# RD.net
KiCad netlist of a schematic drawn in Altium Designer
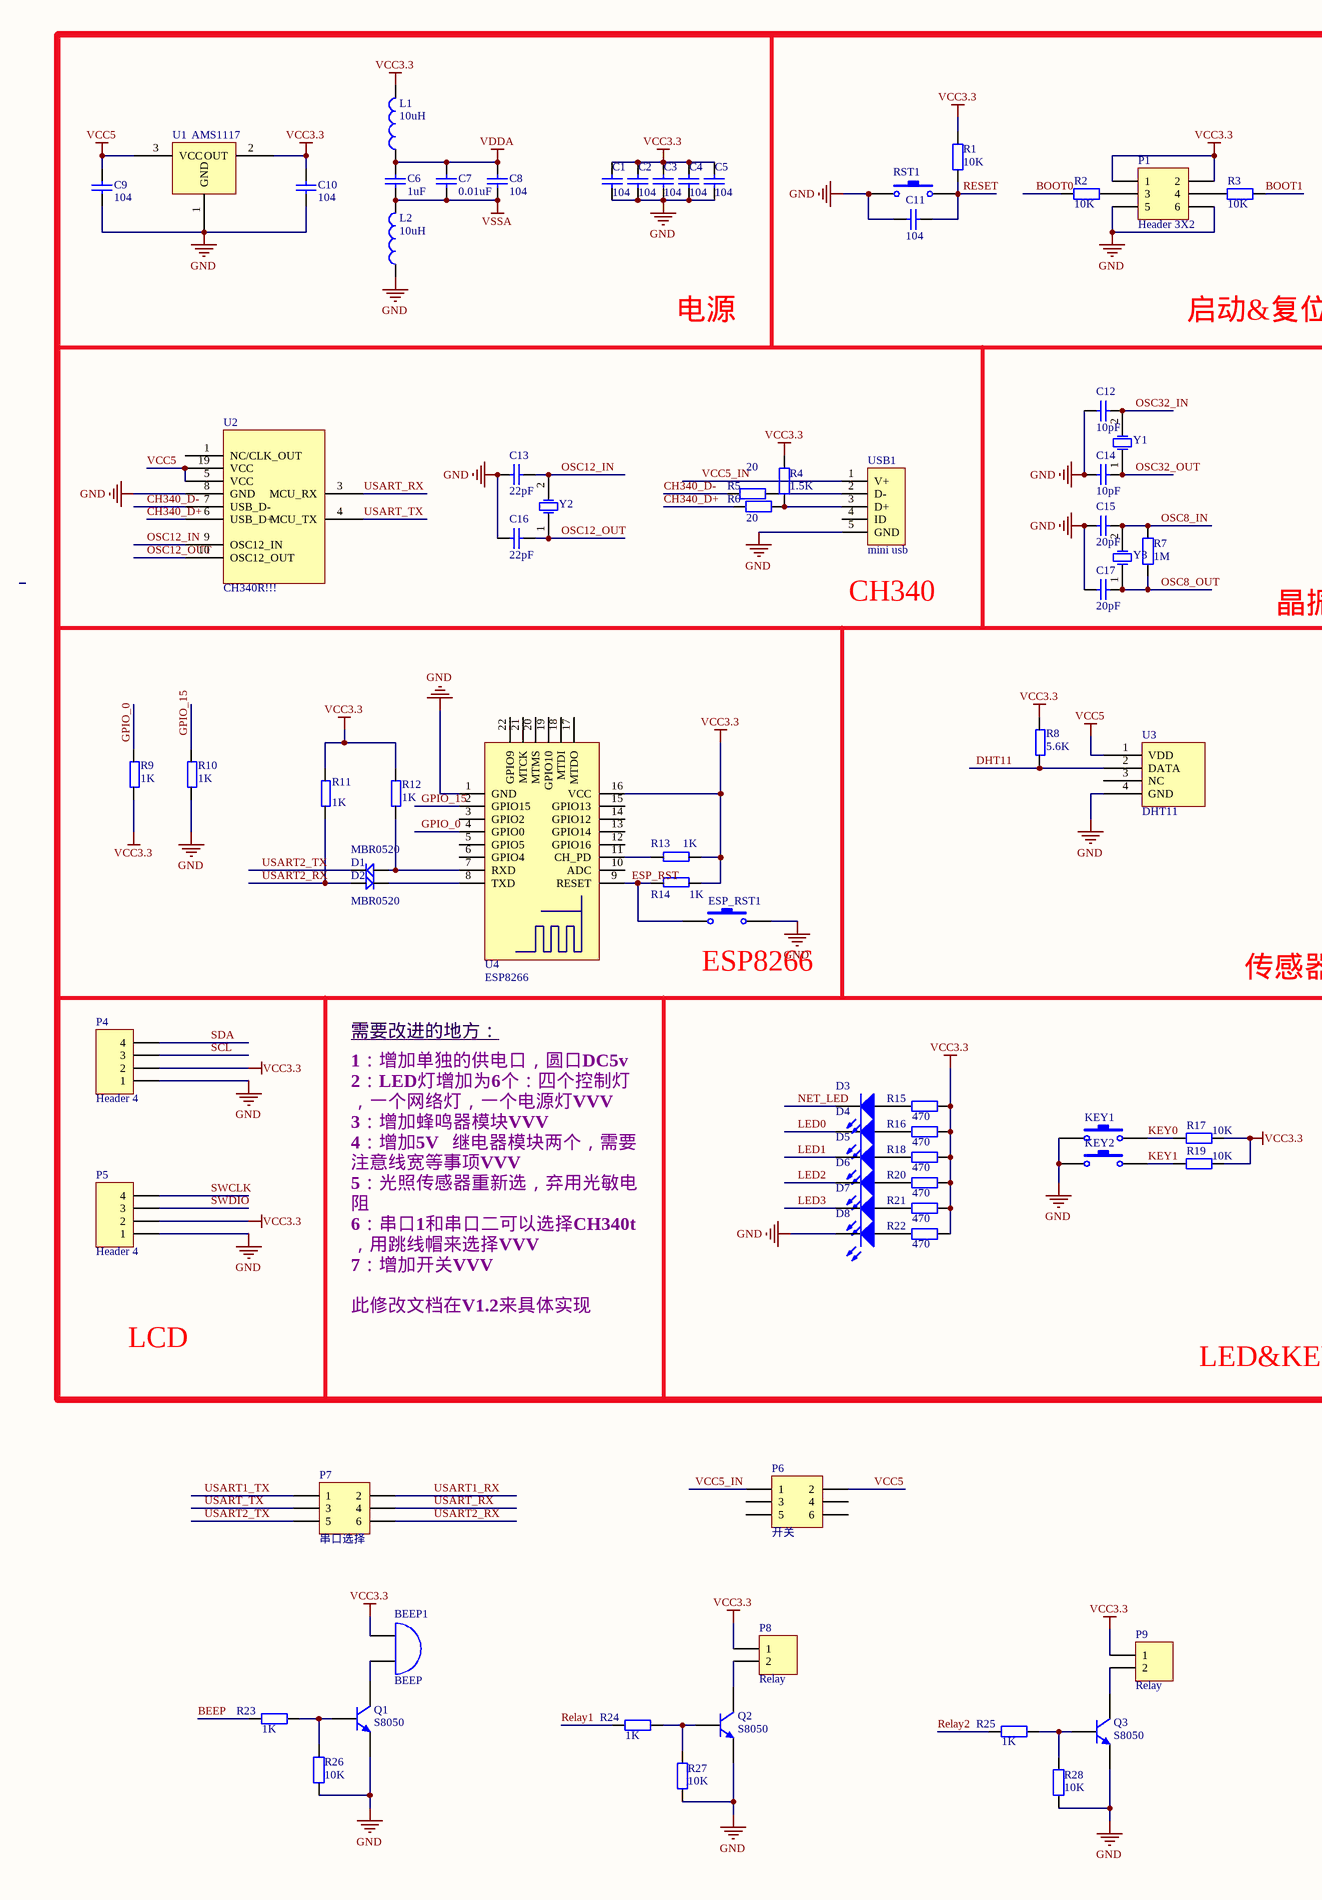
[diagram p0: 云RD.SchDoc, left]
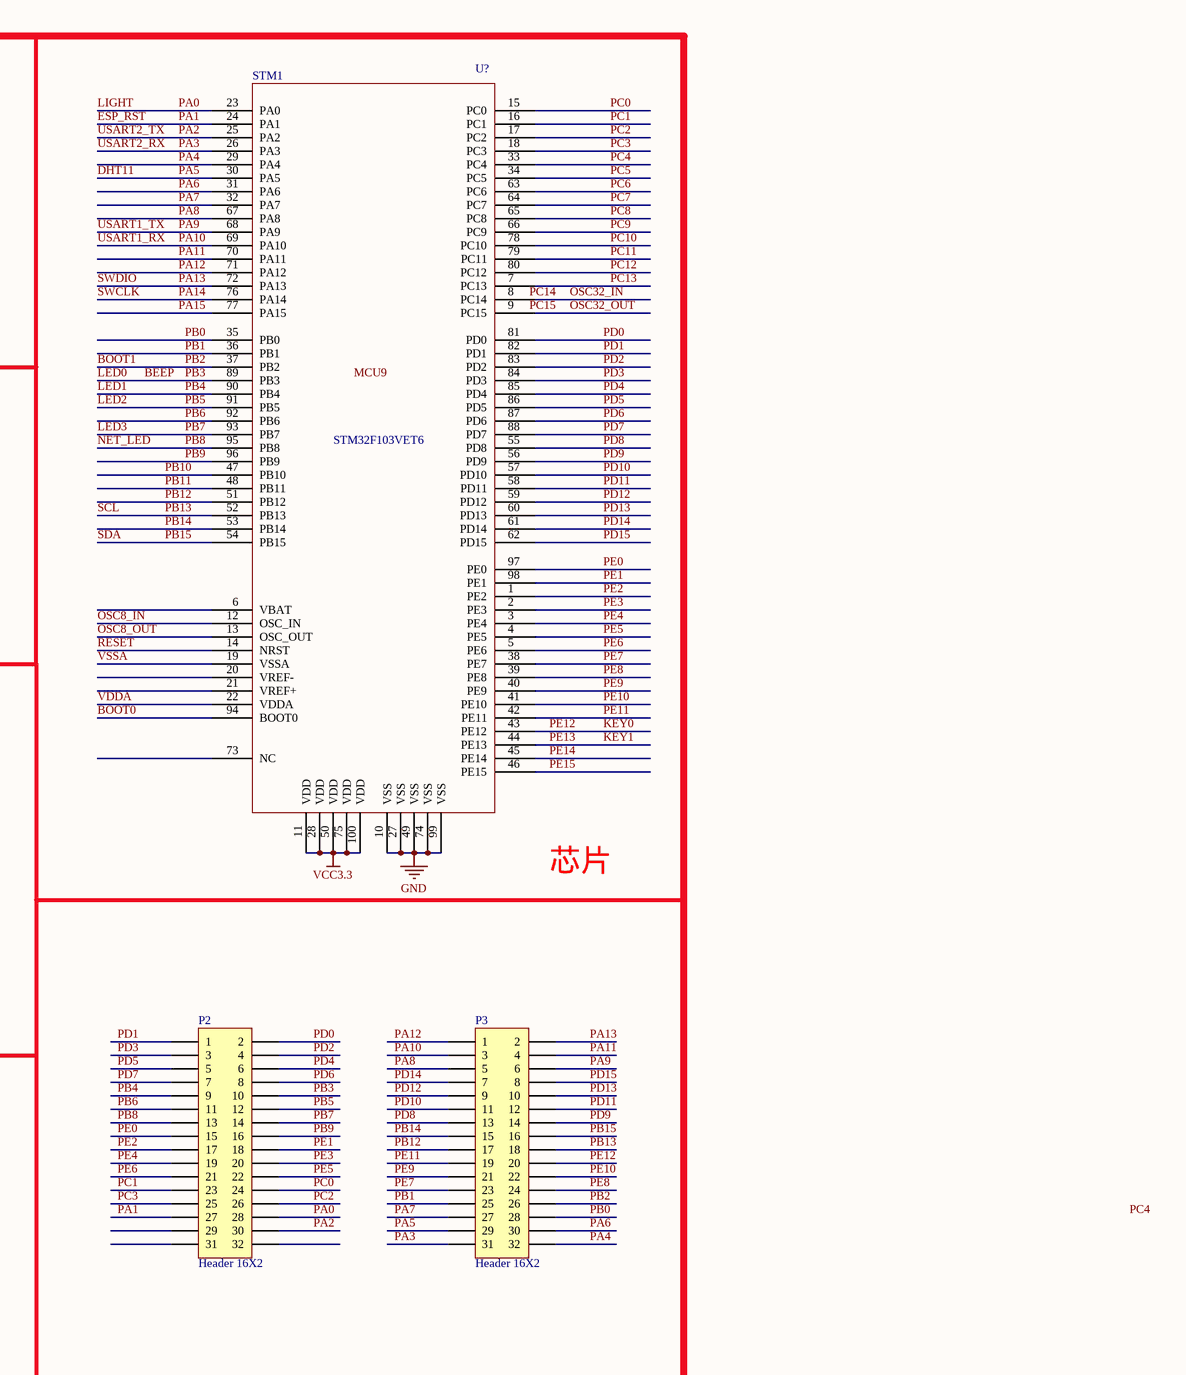
[diagram p1: 云RD.SchDoc, right]

(export (version "E")
  (design (tool "Eeschema 10.0.6"))
  (components
    (comp (ref "BEEP1")
      (value "BEEP")
      (footprint "BEEP")
      (description "Electrical Bell")
      (fields (field (name "PUBLISHER") "Altium Limited"))
      (libsource (lib "Miscellaneous Devices") (part "Bell"))
    )
    (comp (ref "C1")
      (value "104")
      (footprint "0805")
      (description "Capacitor")
      (fields (field (name "Comment") "Cap") (field (name "PUBLISHER") "Altium Limited"))
      (libsource (lib "Miscellaneous Devices") (part "Cap"))
    )
    (comp (ref "C2")
      (value "104")
      (footprint "0805")
      (description "Capacitor")
      (fields (field (name "Comment") "Cap") (field (name "PUBLISHER") "Altium Limited"))
      (libsource (lib "Miscellaneous Devices") (part "Cap"))
    )
    (comp (ref "C3")
      (value "104")
      (footprint "0805")
      (description "Capacitor")
      (fields (field (name "Comment") "Cap") (field (name "PUBLISHER") "Altium Limited"))
      (libsource (lib "Miscellaneous Devices") (part "Cap"))
    )
    (comp (ref "C4")
      (value "104")
      (footprint "0805")
      (description "Capacitor")
      (fields (field (name "Comment") "Cap") (field (name "PUBLISHER") "Altium Limited"))
      (libsource (lib "Miscellaneous Devices") (part "Cap"))
    )
    (comp (ref "C5")
      (value "104")
      (footprint "0805")
      (description "Capacitor")
      (fields (field (name "Comment") "Cap") (field (name "PUBLISHER") "Altium Limited"))
      (libsource (lib "Miscellaneous Devices") (part "Cap"))
    )
    (comp (ref "C6")
      (value "1uF")
      (footprint "0805")
      (description "Capacitor")
      (fields (field (name "Comment") "Cap") (field (name "PUBLISHER") "Altium Limited"))
      (libsource (lib "Miscellaneous Devices") (part "Cap"))
    )
    (comp (ref "C7")
      (value "0.01uF")
      (footprint "0805")
      (description "Capacitor")
      (fields (field (name "Comment") "Cap") (field (name "PUBLISHER") "Altium Limited"))
      (libsource (lib "Miscellaneous Devices") (part "Cap"))
    )
    (comp (ref "C8")
      (value "104")
      (footprint "0805")
      (description "Capacitor")
      (fields (field (name "Comment") "Cap") (field (name "PUBLISHER") "Altium Limited"))
      (libsource (lib "Miscellaneous Devices") (part "Cap"))
    )
    (comp (ref "C9")
      (value "104")
      (footprint "0805")
      (description "Capacitor")
      (fields (field (name "Comment") "Cap") (field (name "PUBLISHER") "Altium Limited"))
      (libsource (lib "Miscellaneous Devices") (part "Cap"))
    )
    (comp (ref "C10")
      (value "104")
      (footprint "0805")
      (description "Capacitor")
      (fields (field (name "Comment") "Cap") (field (name "PUBLISHER") "Altium Limited"))
      (libsource (lib "Miscellaneous Devices") (part "Cap"))
    )
    (comp (ref "C11")
      (value "104")
      (footprint "0805")
      (description "Capacitor")
      (fields (field (name "Comment") "Cap") (field (name "PUBLISHER") "Altium Limited"))
      (libsource (lib "Miscellaneous Devices") (part "Cap"))
    )
    (comp (ref "C12")
      (value "10pF")
      (footprint "0805")
      (description "Capacitor")
      (fields (field (name "Comment") "Cap") (field (name "PUBLISHER") "Altium Limited"))
      (libsource (lib "Miscellaneous Devices") (part "Cap"))
    )
    (comp (ref "C13")
      (value "22pF")
      (footprint "0805")
      (description "Capacitor")
      (fields (field (name "Comment") "Cap") (field (name "PUBLISHER") "Altium Limited"))
      (libsource (lib "Miscellaneous Devices") (part "Cap"))
    )
    (comp (ref "C14")
      (value "10pF")
      (footprint "0805")
      (description "Capacitor")
      (fields (field (name "Comment") "Cap") (field (name "PUBLISHER") "Altium Limited"))
      (libsource (lib "Miscellaneous Devices") (part "Cap"))
    )
    (comp (ref "C15")
      (value "20pF")
      (footprint "0805")
      (description "Capacitor")
      (fields (field (name "Comment") "Cap") (field (name "PUBLISHER") "Altium Limited"))
      (libsource (lib "Miscellaneous Devices") (part "Cap"))
    )
    (comp (ref "C16")
      (value "22pF")
      (footprint "0805")
      (description "Capacitor")
      (fields (field (name "Comment") "Cap") (field (name "PUBLISHER") "Altium Limited"))
      (libsource (lib "Miscellaneous Devices") (part "Cap"))
    )
    (comp (ref "C17")
      (value "20pF")
      (footprint "0805")
      (description "Capacitor")
      (fields (field (name "Comment") "Cap") (field (name "PUBLISHER") "Altium Limited"))
      (libsource (lib "Miscellaneous Devices") (part "Cap"))
    )
    (comp (ref "D1")
      (value "MBR0520")
      (footprint "SOD-123")
      (description "1N4148")
      (libsource (lib "ESP8266V1.2") (part "D"))
    )
    (comp (ref "D2")
      (value "MBR0520")
      (footprint "SOD-123")
      (description "1N4148")
      (libsource (lib "ESP8266V1.2") (part "D"))
    )
    (comp (ref "D3")
      (value "LED1")
      (footprint "0805")
      (description "Typical RED GaAs LED")
      (fields (field (name "PUBLISHER") "Altium Limited"))
      (libsource (lib "Miscellaneous Devices") (part "LED1"))
    )
    (comp (ref "D4")
      (value "LED1")
      (footprint "0805")
      (description "Typical RED GaAs LED")
      (fields (field (name "PUBLISHER") "Altium Limited"))
      (libsource (lib "Miscellaneous Devices") (part "LED1"))
    )
    (comp (ref "D5")
      (value "LED1")
      (footprint "0805")
      (description "Typical RED GaAs LED")
      (fields (field (name "PUBLISHER") "Altium Limited"))
      (libsource (lib "Miscellaneous Devices") (part "LED1"))
    )
    (comp (ref "D6")
      (value "LED1")
      (footprint "0805")
      (description "Typical RED GaAs LED")
      (fields (field (name "PUBLISHER") "Altium Limited"))
      (libsource (lib "Miscellaneous Devices") (part "LED1"))
    )
    (comp (ref "D7")
      (value "LED1")
      (footprint "0805")
      (description "Typical RED GaAs LED")
      (fields (field (name "PUBLISHER") "Altium Limited"))
      (libsource (lib "Miscellaneous Devices") (part "LED1"))
    )
    (comp (ref "D8")
      (value "LED1")
      (footprint "0805")
      (description "Typical RED GaAs LED")
      (fields (field (name "PUBLISHER") "Altium Limited"))
      (libsource (lib "Miscellaneous Devices") (part "LED1"))
    )
    (comp (ref "ESP_RST1")
      (value "SW-PB")
      (footprint "PUSHSW")
      (description "Switch")
      (fields (field (name "PUBLISHER") "Altium Limited"))
      (libsource (lib "gtm900") (part "SW-PB"))
    )
    (comp (ref "KEY1")
      (value "SW-PB")
      (footprint "PUSHSW")
      (description "Switch")
      (fields (field (name "PUBLISHER") "Altium Limited"))
      (libsource (lib "gtm900") (part "SW-PB"))
    )
    (comp (ref "KEY2")
      (value "SW-PB")
      (footprint "PUSHSW")
      (description "Switch")
      (fields (field (name "PUBLISHER") "Altium Limited"))
      (libsource (lib "gtm900") (part "SW-PB"))
    )
    (comp (ref "L1")
      (value "10uH")
      (footprint "0805")
      (description "Inductor")
      (fields (field (name "PUBLISHER") "Altium Limited"))
      (libsource (lib "Miscellaneous Devices") (part "Inductor"))
    )
    (comp (ref "L2")
      (value "10uH")
      (footprint "0805")
      (description "Inductor")
      (fields (field (name "PUBLISHER") "Altium Limited"))
      (libsource (lib "Miscellaneous Devices") (part "Inductor"))
    )
    (comp (ref "P1")
      (value "Header 3X2")
      (footprint "HDR2X3")
      (description "Header, 3-Pin, Dual row")
      (fields (field (name "PUBLISHER") "Altium Limited"))
      (libsource (lib "Miscellaneous Connectors") (part "Header 3X2"))
    )
    (comp (ref "P2")
      (value "Header 16X2")
      (footprint "HDR2X16")
      (description "Header, 16-Pin, Dual row")
      (fields (field (name "PUBLISHER") "Altium Limited"))
      (libsource (lib "Miscellaneous Connectors") (part "Header 16X2"))
    )
    (comp (ref "P3")
      (value "Header 16X2")
      (footprint "HDR2X16")
      (description "Header, 16-Pin, Dual row")
      (fields (field (name "PUBLISHER") "Altium Limited"))
      (libsource (lib "Miscellaneous Connectors") (part "Header 16X2"))
    )
    (comp (ref "P4")
      (value "Header 4")
      (footprint "0.96_OLED")
      (description "Header, 4-Pin")
      (fields (field (name "PUBLISHER") "Altium Limited"))
      (libsource (lib "Miscellaneous Connectors") (part "Header 4"))
    )
    (comp (ref "P5")
      (value "Header 4")
      (footprint "HDR1X4")
      (description "Header, 4-Pin")
      (fields (field (name "PUBLISHER") "Altium Limited"))
      (libsource (lib "Miscellaneous Connectors") (part "Header 4"))
    )
    (comp (ref "P6")
      (value "开关")
      (footprint "开关")
      (description "Header, 3-Pin, Dual row")
      (fields (field (name "PUBLISHER") "Altium Limited"))
      (libsource (lib "Miscellaneous Connectors") (part "Header 3X2"))
    )
    (comp (ref "P7")
      (value "串口选择")
      (footprint "HDR2X3")
      (description "Header, 3-Pin, Dual row")
      (fields (field (name "PUBLISHER") "Altium Limited"))
      (libsource (lib "Miscellaneous Connectors") (part "Header 3X2"))
    )
    (comp (ref "P8")
      (value "Relay")
      (footprint "BEEP")
      (description "Header, 2-Pin")
      (fields (field (name "PUBLISHER") "Altium Limited"))
      (libsource (lib "Miscellaneous Connectors") (part "Header 2"))
    )
    (comp (ref "P9")
      (value "Relay")
      (footprint "BEEP")
      (description "Header, 2-Pin")
      (fields (field (name "PUBLISHER") "Altium Limited"))
      (libsource (lib "Miscellaneous Connectors") (part "Header 2"))
    )
    (comp (ref "Q1")
      (value "S8050")
      (footprint "SOT-23")
      (description "NPN Bipolar Transistor")
      (fields (field (name "PUBLISHER") "Altium Limited"))
      (libsource (lib "Miscellaneous Devices") (part "NPN"))
    )
    (comp (ref "Q2")
      (value "S8050")
      (footprint "SOT-23")
      (description "NPN Bipolar Transistor")
      (fields (field (name "PUBLISHER") "Altium Limited"))
      (libsource (lib "Miscellaneous Devices") (part "NPN"))
    )
    (comp (ref "Q3")
      (value "S8050")
      (footprint "SOT-23")
      (description "NPN Bipolar Transistor")
      (fields (field (name "PUBLISHER") "Altium Limited"))
      (libsource (lib "Miscellaneous Devices") (part "NPN"))
    )
    (comp (ref "R1")
      (value "10K")
      (footprint "0805")
      (description "Resistor")
      (fields (field (name "Comment") "Res2") (field (name "PUBLISHER") "Altium Limited"))
      (libsource (lib "Miscellaneous Devices") (part "Res2"))
    )
    (comp (ref "R2")
      (value "10K")
      (footprint "0805")
      (description "Resistor")
      (fields (field (name "Comment") "Res2") (field (name "PUBLISHER") "Altium Limited"))
      (libsource (lib "") (part "Res2_2"))
    )
    (comp (ref "R3")
      (value "10K")
      (footprint "0805")
      (description "Resistor")
      (fields (field (name "Comment") "Res2") (field (name "PUBLISHER") "Altium Limited"))
      (libsource (lib "") (part "Res2_2"))
    )
    (comp (ref "R4")
      (value "1.5K")
      (footprint "0805")
      (description "Resistor")
      (fields (field (name "Comment") "Res2") (field (name "PUBLISHER") "Altium Limited"))
      (libsource (lib "") (part "Res2_3"))
    )
    (comp (ref "R5")
      (value "20")
      (footprint "0805")
      (description "Resistor")
      (fields (field (name "Comment") "Res2") (field (name "PUBLISHER") "Altium Limited"))
      (libsource (lib "Miscellaneous Devices") (part "Res2"))
    )
    (comp (ref "R6")
      (value "20")
      (footprint "0805")
      (description "Resistor")
      (fields (field (name "Comment") "Res2") (field (name "PUBLISHER") "Altium Limited"))
      (libsource (lib "Miscellaneous Devices") (part "Res2"))
    )
    (comp (ref "R7")
      (value "1M")
      (footprint "0805")
      (description "Resistor")
      (fields (field (name "Comment") "Res2") (field (name "PUBLISHER") "Altium Limited"))
      (libsource (lib "") (part "Res2_3"))
    )
    (comp (ref "R8") (value "5.6K") (footprint "0805") (libsource (lib "ESP8266V1.2") (part "R")))
    (comp (ref "R9") (value "1K") (footprint "0805") (libsource (lib "ESP8266V1.2") (part "R")))
    (comp (ref "R10") (value "1K") (footprint "0805") (libsource (lib "ESP8266V1.2") (part "R")))
    (comp (ref "R11") (value "1K") (footprint "0805") (libsource (lib "ESP8266V1.2") (part "R")))
    (comp (ref "R12") (value "1K") (footprint "0805") (libsource (lib "ESP8266V1.2") (part "R")))
    (comp (ref "R13") (value "1K") (footprint "0805") (libsource (lib "ESP8266V1.2") (part "R")))
    (comp (ref "R14") (value "1K") (footprint "0805") (libsource (lib "ESP8266V1.2") (part "R")))
    (comp (ref "R15")
      (value "470")
      (footprint "0805")
      (description "Resistor")
      (fields (field (name "Comment") "Res2") (field (name "PUBLISHER") "Altium Limited"))
      (libsource (lib "Miscellaneous Devices") (part "Res2"))
    )
    (comp (ref "R16")
      (value "470")
      (footprint "0805")
      (description "Resistor")
      (fields (field (name "Comment") "Res2") (field (name "PUBLISHER") "Altium Limited"))
      (libsource (lib "Miscellaneous Devices") (part "Res2"))
    )
    (comp (ref "R17")
      (value "10K")
      (footprint "0805")
      (description "Resistor")
      (fields (field (name "Comment") "Res2") (field (name "PUBLISHER") "Altium Limited"))
      (libsource (lib "Miscellaneous Devices") (part "Res2"))
    )
    (comp (ref "R18")
      (value "470")
      (footprint "0805")
      (description "Resistor")
      (fields (field (name "Comment") "Res2") (field (name "PUBLISHER") "Altium Limited"))
      (libsource (lib "Miscellaneous Devices") (part "Res2"))
    )
    (comp (ref "R19")
      (value "10K")
      (footprint "0805")
      (description "Resistor")
      (fields (field (name "Comment") "Res2") (field (name "PUBLISHER") "Altium Limited"))
      (libsource (lib "Miscellaneous Devices") (part "Res2"))
    )
    (comp (ref "R20")
      (value "470")
      (footprint "0805")
      (description "Resistor")
      (fields (field (name "Comment") "Res2") (field (name "PUBLISHER") "Altium Limited"))
      (libsource (lib "Miscellaneous Devices") (part "Res2"))
    )
    (comp (ref "R21")
      (value "470")
      (footprint "0805")
      (description "Resistor")
      (fields (field (name "Comment") "Res2") (field (name "PUBLISHER") "Altium Limited"))
      (libsource (lib "Miscellaneous Devices") (part "Res2"))
    )
    (comp (ref "R22")
      (value "470")
      (footprint "0805")
      (description "Resistor")
      (fields (field (name "Comment") "Res2") (field (name "PUBLISHER") "Altium Limited"))
      (libsource (lib "Miscellaneous Devices") (part "Res2"))
    )
    (comp (ref "R23")
      (value "1K")
      (footprint "0805")
      (description "Resistor")
      (fields (field (name "Comment") "Res2") (field (name "PUBLISHER") "Altium Limited"))
      (libsource (lib "Miscellaneous Devices") (part "Res2"))
    )
    (comp (ref "R24")
      (value "1K")
      (footprint "0805")
      (description "Resistor")
      (fields (field (name "Comment") "Res2") (field (name "PUBLISHER") "Altium Limited"))
      (libsource (lib "Miscellaneous Devices") (part "Res2"))
    )
    (comp (ref "R25")
      (value "1K")
      (footprint "0805")
      (description "Resistor")
      (fields (field (name "Comment") "Res2") (field (name "PUBLISHER") "Altium Limited"))
      (libsource (lib "Miscellaneous Devices") (part "Res2"))
    )
    (comp (ref "R26")
      (value "10K")
      (footprint "0805")
      (description "Resistor")
      (fields (field (name "Comment") "Res2") (field (name "PUBLISHER") "Altium Limited"))
      (libsource (lib "") (part "Res2_1"))
    )
    (comp (ref "R27")
      (value "10K")
      (footprint "0805")
      (description "Resistor")
      (fields (field (name "Comment") "Res2") (field (name "PUBLISHER") "Altium Limited"))
      (libsource (lib "") (part "Res2_1"))
    )
    (comp (ref "R28")
      (value "10K")
      (footprint "0805")
      (description "Resistor")
      (fields (field (name "Comment") "Res2") (field (name "PUBLISHER") "Altium Limited"))
      (libsource (lib "") (part "Res2_1"))
    )
    (comp (ref "RST1")
      (value "SW-PB")
      (footprint "PUSHSW")
      (description "Switch")
      (fields (field (name "PUBLISHER") "Altium Limited"))
      (libsource (lib "gtm900") (part "SW-PB"))
    )
    (comp (ref "STM1") (value "U?") (footprint "LQFP100") (libsource (lib "云RD") (part "STM32f103VET6")))
    (comp (ref "U1") (value "AMS1117") (footprint "SOT223") (libsource (lib "STM32schlib") (part "AMS")))
    (comp (ref "U2") (value "CH340R!!!") (footprint "ch340T") (libsource (lib "Schlib1") (part "CH340")))
    (comp (ref "U3") (value "DHT11") (footprint "HDR1X4 - duplicate") (libsource (lib "云RD") (part "DHT11")))
    (comp (ref "U4") (value "ESP8266") (footprint "ESP8266") (libsource (lib "ESP8266V1.2") (part "ESP8266")))
    (comp (ref "USB1")
      (value "mini usb")
      (footprint "MICRO-USB")
      (libsource (lib "Schlib1") (part "mini usb"))
    )
    (comp (ref "Y1")
      (value "XTAL")
      (footprint "XTL")
      (description "Crystal Oscillator")
      (fields (field (name "PUBLISHER") "Altium Limited"))
      (libsource (lib "Miscellaneous Devices") (part "XTAL"))
    )
    (comp (ref "Y2")
      (value "XTAL")
      (footprint "XTAL5")
      (description "Crystal Oscillator")
      (fields (field (name "PUBLISHER") "Altium Limited"))
      (libsource (lib "Miscellaneous Devices") (part "XTAL"))
    )
    (comp (ref "Y3")
      (value "XTAL")
      (footprint "XTAL5")
      (description "Crystal Oscillator")
      (fields (field (name "PUBLISHER") "Altium Limited"))
      (libsource (lib "Miscellaneous Devices") (part "XTAL"))
    )
  )
  (nets
    (net (code "1") (name "/BEEP") (class "Default")
      (node (ref "D4") (pin "2") (pinfunction "K_2") (pintype "passive"))
      (node (ref "P2") (pin "10") (pinfunction "10_10") (pintype "passive"))
      (node (ref "R23") (pin "2") (pinfunction "2_2") (pintype "passive"))
      (node (ref "STM1") (pin "89") (pinfunction "PB3_89") (pintype "passive"))
    )
    (net (code "2") (name "/BOOT0") (class "Default")
      (node (ref "R2") (pin "1") (pinfunction "1_1") (pintype "passive"))
      (node (ref "STM1") (pin "94") (pinfunction "BOOT0_94") (pintype "passive"))
    )
    (net (code "3") (name "/BOOT1") (class "Default")
      (node (ref "P3") (pin "26") (pinfunction "26_26") (pintype "passive"))
      (node (ref "R3") (pin "2") (pinfunction "2_2") (pintype "passive"))
      (node (ref "STM1") (pin "37") (pinfunction "PB2_37") (pintype "passive"))
    )
    (net (code "4") (name "/CH340_D+") (class "Default")
      (node (ref "R6") (pin "2") (pinfunction "2_2") (pintype "passive"))
      (node (ref "U2") (pin "6") (pinfunction "USB_D+_6") (pintype "passive"))
    )
    (net (code "5") (name "/CH340_D-") (class "Default")
      (node (ref "R5") (pin "2") (pinfunction "2_2") (pintype "passive"))
      (node (ref "U2") (pin "7") (pinfunction "USB_D-_7") (pintype "passive"))
    )
    (net (code "6") (name "/DHT11") (class "Default")
      (node (ref "P3") (pin "29") (pinfunction "29_29") (pintype "passive"))
      (node (ref "R8") (pin "1") (pintype "passive"))
      (node (ref "STM1") (pin "30") (pinfunction "PA5_30") (pintype "passive"))
      (node (ref "U3") (pin "2") (pinfunction "DATA_2") (pintype "passive"))
    )
    (net (code "7") (name "/ESP_RST") (class "Default")
      (node (ref "ESP_RST1") (pin "1") (pinfunction "1_1") (pintype "passive"))
      (node (ref "P2") (pin "27") (pinfunction "27_27") (pintype "passive"))
      (node (ref "R14") (pin "2") (pintype "passive"))
      (node (ref "STM1") (pin "24") (pinfunction "PA1_24") (pintype "passive"))
      (node (ref "U4") (pin "9") (pinfunction "RESET_9") (pintype "passive"))
    )
    (net (code "8") (name "/GPIO_0") (class "Default")
      (node (ref "R9") (pin "2") (pintype "passive"))
      (node (ref "U4") (pin "4") (pinfunction "GPIO0_4") (pintype "passive"))
    )
    (net (code "9") (name "/GPIO_15") (class "Default")
      (node (ref "R10") (pin "2") (pintype "passive"))
      (node (ref "U4") (pin "2") (pinfunction "GPIO15_2") (pintype "passive"))
    )
    (net (code "10") (name "/KEY0") (class "Default")
      (node (ref "KEY1") (pin "2") (pinfunction "2_2") (pintype "passive"))
      (node (ref "P3") (pin "20") (pinfunction "20_20") (pintype "passive"))
      (node (ref "R17") (pin "2") (pinfunction "2_2") (pintype "passive"))
      (node (ref "STM1") (pin "43") (pinfunction "PE12_43") (pintype "passive"))
    )
    (net (code "11") (name "/KEY1") (class "Default")
      (node (ref "KEY2") (pin "2") (pinfunction "2_2") (pintype "passive"))
      (node (ref "R19") (pin "2") (pinfunction "2_2") (pintype "passive"))
      (node (ref "STM1") (pin "44") (pinfunction "PE13_44") (pintype "passive"))
    )
    (net (code "12") (name "/LED1") (class "Default")
      (node (ref "D5") (pin "2") (pinfunction "K_2") (pintype "passive"))
      (node (ref "P2") (pin "9") (pinfunction "9_9") (pintype "passive"))
      (node (ref "STM1") (pin "90") (pinfunction "PB4_90") (pintype "passive"))
    )
    (net (code "13") (name "/LED2") (class "Default")
      (node (ref "D6") (pin "2") (pinfunction "K_2") (pintype "passive"))
      (node (ref "P2") (pin "12") (pinfunction "12_12") (pintype "passive"))
      (node (ref "STM1") (pin "91") (pinfunction "PB5_91") (pintype "passive"))
    )
    (net (code "14") (name "/LED3") (class "Default")
      (node (ref "D7") (pin "2") (pinfunction "K_2") (pintype "passive"))
      (node (ref "P2") (pin "14") (pinfunction "14_14") (pintype "passive"))
      (node (ref "STM1") (pin "93") (pinfunction "PB7_93") (pintype "passive"))
    )
    (net (code "15") (name "/LIGHT") (class "Default")
      (node (ref "P2") (pin "28") (pinfunction "28_28") (pintype "passive"))
      (node (ref "STM1") (pin "23") (pinfunction "PA0_23") (pintype "passive"))
    )
    (net (code "17") (name "/NET_LED") (class "Default")
      (node (ref "D3") (pin "2") (pinfunction "K_2") (pintype "passive"))
      (node (ref "P2") (pin "13") (pinfunction "13_13") (pintype "passive"))
      (node (ref "STM1") (pin "95") (pinfunction "PB8_95") (pintype "passive"))
    )
    (net (code "18") (name "/OSC8_IN") (class "Default")
      (node (ref "C15") (pin "2") (pinfunction "2_2") (pintype "passive"))
      (node (ref "R7") (pin "2") (pinfunction "2_2") (pintype "passive"))
      (node (ref "STM1") (pin "12") (pinfunction "OSC_IN_12") (pintype "passive"))
      (node (ref "Y3") (pin "2") (pinfunction "OSC2_2") (pintype "passive"))
    )
    (net (code "19") (name "/OSC8_OUT") (class "Default")
      (node (ref "C17") (pin "2") (pinfunction "2_2") (pintype "passive"))
      (node (ref "R7") (pin "1") (pinfunction "1_1") (pintype "passive"))
      (node (ref "STM1") (pin "13") (pinfunction "OSC_OUT_13") (pintype "passive"))
      (node (ref "Y3") (pin "1") (pinfunction "OSC1_1") (pintype "passive"))
    )
    (net (code "20") (name "/OSC12_IN") (class "Default")
      (node (ref "C13") (pin "2") (pinfunction "2_2") (pintype "passive"))
      (node (ref "U2") (pin "9") (pinfunction "OSC12_IN_9") (pintype "passive"))
      (node (ref "Y2") (pin "2") (pinfunction "OSC2_2") (pintype "passive"))
    )
    (net (code "21") (name "/OSC12_OUT") (class "Default")
      (node (ref "C16") (pin "2") (pinfunction "2_2") (pintype "passive"))
      (node (ref "U2") (pin "10") (pinfunction "OSC12_OUT_10") (pintype "passive"))
      (node (ref "Y2") (pin "1") (pinfunction "OSC1_1") (pintype "passive"))
    )
    (net (code "22") (name "/OSC32_IN") (class "Default")
      (node (ref "C12") (pin "2") (pinfunction "2_2") (pintype "passive"))
      (node (ref "STM1") (pin "8") (pinfunction "PC14_8") (pintype "passive"))
      (node (ref "Y1") (pin "2") (pinfunction "OSC2_2") (pintype "passive"))
    )
    (net (code "23") (name "/OSC32_OUT") (class "Default")
      (node (ref "C14") (pin "2") (pinfunction "2_2") (pintype "passive"))
      (node (ref "STM1") (pin "9") (pinfunction "PC15_9") (pintype "passive"))
      (node (ref "Y1") (pin "1") (pinfunction "OSC1_1") (pintype "passive"))
    )
    (net (code "24") (name "/PA2") (class "Default")
      (node (ref "D1") (pin "2") (pintype "passive"))
      (node (ref "P2") (pin "30") (pinfunction "30_30") (pintype "passive"))
      (node (ref "P7") (pin "5") (pinfunction "5_5") (pintype "passive"))
      (node (ref "STM1") (pin "25") (pinfunction "PA2_25") (pintype "passive"))
    )
    (net (code "25") (name "/PA3") (class "Default")
      (node (ref "D2") (pin "1") (pintype "passive"))
      (node (ref "P3") (pin "31") (pinfunction "31_31") (pintype "passive"))
      (node (ref "P7") (pin "6") (pinfunction "6_6") (pintype "passive"))
      (node (ref "R11") (pin "1") (pintype "passive"))
      (node (ref "STM1") (pin "26") (pinfunction "PA3_26") (pintype "passive"))
    )
    (net (code "26") (name "/PA4") (class "Default")
      (node (ref "P3") (pin "32") (pinfunction "32_32") (pintype "passive"))
      (node (ref "STM1") (pin "29") (pinfunction "PA4_29") (pintype "passive"))
    )
    (net (code "27") (name "/PA6") (class "Default")
      (node (ref "P3") (pin "30") (pinfunction "30_30") (pintype "passive"))
      (node (ref "STM1") (pin "31") (pinfunction "PA6_31") (pintype "passive"))
    )
    (net (code "28") (name "/PA7") (class "Default")
      (node (ref "P3") (pin "27") (pinfunction "27_27") (pintype "passive"))
      (node (ref "STM1") (pin "32") (pinfunction "PA7_32") (pintype "passive"))
    )
    (net (code "29") (name "/PA8") (class "Default")
      (node (ref "P3") (pin "5") (pinfunction "5_5") (pintype "passive"))
      (node (ref "STM1") (pin "67") (pinfunction "PA8_67") (pintype "passive"))
    )
    (net (code "30") (name "/PA9") (class "Default")
      (node (ref "P3") (pin "6") (pinfunction "6_6") (pintype "passive"))
      (node (ref "P7") (pin "1") (pinfunction "1_1") (pintype "passive"))
      (node (ref "STM1") (pin "68") (pinfunction "PA9_68") (pintype "passive"))
    )
    (net (code "31") (name "/PA10") (class "Default")
      (node (ref "P3") (pin "3") (pinfunction "3_3") (pintype "passive"))
      (node (ref "P7") (pin "2") (pinfunction "2_2") (pintype "passive"))
      (node (ref "STM1") (pin "69") (pinfunction "PA10_69") (pintype "passive"))
    )
    (net (code "32") (name "/PA11") (class "Default")
      (node (ref "P3") (pin "4") (pinfunction "4_4") (pintype "passive"))
      (node (ref "STM1") (pin "70") (pinfunction "PA11_70") (pintype "passive"))
    )
    (net (code "33") (name "/PA12") (class "Default")
      (node (ref "P3") (pin "1") (pinfunction "1_1") (pintype "passive"))
      (node (ref "STM1") (pin "71") (pinfunction "PA12_71") (pintype "passive"))
    )
    (net (code "34") (name "/PA13") (class "Default")
      (node (ref "P3") (pin "2") (pinfunction "2_2") (pintype "passive"))
      (node (ref "P5") (pin "3") (pinfunction "3_3") (pintype "passive"))
      (node (ref "STM1") (pin "72") (pinfunction "PA13_72") (pintype "passive"))
    )
    (net (code "35") (name "/PA14") (class "Default")
      (node (ref "P5") (pin "4") (pinfunction "4_4") (pintype "passive"))
      (node (ref "STM1") (pin "76") (pinfunction "PA14_76") (pintype "passive"))
    )
    (net (code "36") (name "/PA15") (class "Default")
      (node (ref "STM1") (pin "77") (pinfunction "PA15_77") (pintype "passive"))
    )
    (net (code "37") (name "/PB0") (class "Default")
      (node (ref "P3") (pin "28") (pinfunction "28_28") (pintype "passive"))
      (node (ref "STM1") (pin "35") (pinfunction "PB0_35") (pintype "passive"))
    )
    (net (code "38") (name "/PB1") (class "Default")
      (node (ref "P3") (pin "25") (pinfunction "25_25") (pintype "passive"))
      (node (ref "STM1") (pin "36") (pinfunction "PB1_36") (pintype "passive"))
    )
    (net (code "39") (name "/PB6") (class "Default")
      (node (ref "P2") (pin "11") (pinfunction "11_11") (pintype "passive"))
      (node (ref "STM1") (pin "92") (pinfunction "PB6_92") (pintype "passive"))
    )
    (net (code "40") (name "/PB9") (class "Default")
      (node (ref "P2") (pin "16") (pinfunction "16_16") (pintype "passive"))
      (node (ref "STM1") (pin "96") (pinfunction "PB9_96") (pintype "passive"))
    )
    (net (code "41") (name "/PB10") (class "Default")
      (node (ref "STM1") (pin "47") (pinfunction "PB10_47") (pintype "passive"))
    )
    (net (code "42") (name "/PB11") (class "Default")
      (node (ref "STM1") (pin "48") (pinfunction "PB11_48") (pintype "passive"))
    )
    (net (code "43") (name "/PB12") (class "Default")
      (node (ref "P3") (pin "17") (pinfunction "17_17") (pintype "passive"))
      (node (ref "STM1") (pin "51") (pinfunction "PB12_51") (pintype "passive"))
    )
    (net (code "44") (name "/PB13") (class "Default")
      (node (ref "P3") (pin "18") (pinfunction "18_18") (pintype "passive"))
      (node (ref "P4") (pin "3") (pinfunction "3_3") (pintype "passive"))
      (node (ref "STM1") (pin "52") (pinfunction "PB13_52") (pintype "passive"))
    )
    (net (code "45") (name "/PB14") (class "Default")
      (node (ref "P3") (pin "15") (pinfunction "15_15") (pintype "passive"))
      (node (ref "STM1") (pin "53") (pinfunction "PB14_53") (pintype "passive"))
    )
    (net (code "46") (name "/PB15") (class "Default")
      (node (ref "P3") (pin "16") (pinfunction "16_16") (pintype "passive"))
      (node (ref "P4") (pin "4") (pinfunction "4_4") (pintype "passive"))
      (node (ref "STM1") (pin "54") (pinfunction "PB15_54") (pintype "passive"))
    )
    (net (code "47") (name "/PC0") (class "Default")
      (node (ref "P2") (pin "24") (pinfunction "24_24") (pintype "passive"))
      (node (ref "STM1") (pin "15") (pinfunction "PC0_15") (pintype "passive"))
    )
    (net (code "48") (name "/PC1") (class "Default")
      (node (ref "P2") (pin "23") (pinfunction "23_23") (pintype "passive"))
      (node (ref "STM1") (pin "16") (pinfunction "PC1_16") (pintype "passive"))
    )
    (net (code "49") (name "/PC2") (class "Default")
      (node (ref "P2") (pin "26") (pinfunction "26_26") (pintype "passive"))
      (node (ref "STM1") (pin "17") (pinfunction "PC2_17") (pintype "passive"))
    )
    (net (code "50") (name "/PC3") (class "Default")
      (node (ref "P2") (pin "25") (pinfunction "25_25") (pintype "passive"))
      (node (ref "STM1") (pin "18") (pinfunction "PC3_18") (pintype "passive"))
    )
    (net (code "51") (name "/PC4") (class "Default")
      (node (ref "STM1") (pin "33") (pinfunction "PC4_33") (pintype "passive"))
    )
    (net (code "52") (name "/PC5") (class "Default")
      (node (ref "STM1") (pin "34") (pinfunction "PC5_34") (pintype "passive"))
    )
    (net (code "53") (name "/PC6") (class "Default")
      (node (ref "STM1") (pin "63") (pinfunction "PC6_63") (pintype "passive"))
    )
    (net (code "54") (name "/PC7") (class "Default")
      (node (ref "STM1") (pin "64") (pinfunction "PC7_64") (pintype "passive"))
    )
    (net (code "55") (name "/PC8") (class "Default")
      (node (ref "STM1") (pin "65") (pinfunction "PC8_65") (pintype "passive"))
    )
    (net (code "56") (name "/PC9") (class "Default")
      (node (ref "STM1") (pin "66") (pinfunction "PC9_66") (pintype "passive"))
    )
    (net (code "57") (name "/PC10") (class "Default")
      (node (ref "STM1") (pin "78") (pinfunction "PC10_78") (pintype "passive"))
    )
    (net (code "58") (name "/PC11") (class "Default")
      (node (ref "STM1") (pin "79") (pinfunction "PC11_79") (pintype "passive"))
    )
    (net (code "59") (name "/PC12") (class "Default")
      (node (ref "STM1") (pin "80") (pinfunction "PC12_80") (pintype "passive"))
    )
    (net (code "60") (name "/PC13") (class "Default")
      (node (ref "STM1") (pin "7") (pinfunction "PC13_7") (pintype "passive"))
    )
    (net (code "63") (name "/PD0") (class "Default")
      (node (ref "P2") (pin "2") (pinfunction "2_2") (pintype "passive"))
      (node (ref "STM1") (pin "81") (pinfunction "PD0_81") (pintype "passive"))
    )
    (net (code "64") (name "/PD1") (class "Default")
      (node (ref "P2") (pin "1") (pinfunction "1_1") (pintype "passive"))
      (node (ref "STM1") (pin "82") (pinfunction "PD1_82") (pintype "passive"))
    )
    (net (code "65") (name "/PD2") (class "Default")
      (node (ref "P2") (pin "4") (pinfunction "4_4") (pintype "passive"))
      (node (ref "STM1") (pin "83") (pinfunction "PD2_83") (pintype "passive"))
    )
    (net (code "66") (name "/PD3") (class "Default")
      (node (ref "P2") (pin "3") (pinfunction "3_3") (pintype "passive"))
      (node (ref "STM1") (pin "84") (pinfunction "PD3_84") (pintype "passive"))
    )
    (net (code "67") (name "/PD4") (class "Default")
      (node (ref "P2") (pin "6") (pinfunction "6_6") (pintype "passive"))
      (node (ref "STM1") (pin "85") (pinfunction "PD4_85") (pintype "passive"))
    )
    (net (code "68") (name "/PD5") (class "Default")
      (node (ref "P2") (pin "5") (pinfunction "5_5") (pintype "passive"))
      (node (ref "STM1") (pin "86") (pinfunction "PD5_86") (pintype "passive"))
    )
    (net (code "69") (name "/PD6") (class "Default")
      (node (ref "P2") (pin "8") (pinfunction "8_8") (pintype "passive"))
      (node (ref "STM1") (pin "87") (pinfunction "PD6_87") (pintype "passive"))
    )
    (net (code "70") (name "/PD7") (class "Default")
      (node (ref "P2") (pin "7") (pinfunction "7_7") (pintype "passive"))
      (node (ref "STM1") (pin "88") (pinfunction "PD7_88") (pintype "passive"))
    )
    (net (code "71") (name "/PD8") (class "Default")
      (node (ref "P3") (pin "13") (pinfunction "13_13") (pintype "passive"))
      (node (ref "STM1") (pin "55") (pinfunction "PD8_55") (pintype "passive"))
    )
    (net (code "72") (name "/PD9") (class "Default")
      (node (ref "P3") (pin "14") (pinfunction "14_14") (pintype "passive"))
      (node (ref "STM1") (pin "56") (pinfunction "PD9_56") (pintype "passive"))
    )
    (net (code "73") (name "/PD10") (class "Default")
      (node (ref "P3") (pin "11") (pinfunction "11_11") (pintype "passive"))
      (node (ref "STM1") (pin "57") (pinfunction "PD10_57") (pintype "passive"))
    )
    (net (code "74") (name "/PD11") (class "Default")
      (node (ref "P3") (pin "12") (pinfunction "12_12") (pintype "passive"))
      (node (ref "STM1") (pin "58") (pinfunction "PD11_58") (pintype "passive"))
    )
    (net (code "75") (name "/PD12") (class "Default")
      (node (ref "P3") (pin "9") (pinfunction "9_9") (pintype "passive"))
      (node (ref "STM1") (pin "59") (pinfunction "PD12_59") (pintype "passive"))
    )
    (net (code "76") (name "/PD13") (class "Default")
      (node (ref "P3") (pin "10") (pinfunction "10_10") (pintype "passive"))
      (node (ref "STM1") (pin "60") (pinfunction "PD13_60") (pintype "passive"))
    )
    (net (code "77") (name "/PD14") (class "Default")
      (node (ref "P3") (pin "7") (pinfunction "7_7") (pintype "passive"))
      (node (ref "STM1") (pin "61") (pinfunction "PD14_61") (pintype "passive"))
    )
    (net (code "78") (name "/PD15") (class "Default")
      (node (ref "P3") (pin "8") (pinfunction "8_8") (pintype "passive"))
      (node (ref "STM1") (pin "62") (pinfunction "PD15_62") (pintype "passive"))
    )
    (net (code "79") (name "/PE0") (class "Default")
      (node (ref "P2") (pin "15") (pinfunction "15_15") (pintype "passive"))
      (node (ref "STM1") (pin "97") (pinfunction "PE0_97") (pintype "passive"))
    )
    (net (code "80") (name "/PE1") (class "Default")
      (node (ref "P2") (pin "18") (pinfunction "18_18") (pintype "passive"))
      (node (ref "STM1") (pin "98") (pinfunction "PE1_98") (pintype "passive"))
    )
    (net (code "81") (name "/PE2") (class "Default")
      (node (ref "P2") (pin "17") (pinfunction "17_17") (pintype "passive"))
      (node (ref "STM1") (pin "1") (pinfunction "PE2_1") (pintype "passive"))
    )
    (net (code "82") (name "/PE3") (class "Default")
      (node (ref "P2") (pin "20") (pinfunction "20_20") (pintype "passive"))
      (node (ref "STM1") (pin "2") (pinfunction "PE3_2") (pintype "passive"))
    )
    (net (code "83") (name "/PE4") (class "Default")
      (node (ref "P2") (pin "19") (pinfunction "19_19") (pintype "passive"))
      (node (ref "STM1") (pin "3") (pinfunction "PE4_3") (pintype "passive"))
    )
    (net (code "84") (name "/PE5") (class "Default")
      (node (ref "P2") (pin "22") (pinfunction "22_22") (pintype "passive"))
      (node (ref "STM1") (pin "4") (pinfunction "PE5_4") (pintype "passive"))
    )
    (net (code "85") (name "/PE6") (class "Default")
      (node (ref "P2") (pin "21") (pinfunction "21_21") (pintype "passive"))
      (node (ref "STM1") (pin "5") (pinfunction "PE6_5") (pintype "passive"))
    )
    (net (code "86") (name "/PE7") (class "Default")
      (node (ref "P3") (pin "23") (pinfunction "23_23") (pintype "passive"))
      (node (ref "STM1") (pin "38") (pinfunction "PE7_38") (pintype "passive"))
    )
    (net (code "87") (name "/PE8") (class "Default")
      (node (ref "P3") (pin "24") (pinfunction "24_24") (pintype "passive"))
      (node (ref "STM1") (pin "39") (pinfunction "PE8_39") (pintype "passive"))
    )
    (net (code "88") (name "/PE9") (class "Default")
      (node (ref "P3") (pin "21") (pinfunction "21_21") (pintype "passive"))
      (node (ref "STM1") (pin "40") (pinfunction "PE9_40") (pintype "passive"))
    )
    (net (code "89") (name "/PE10") (class "Default")
      (node (ref "P3") (pin "22") (pinfunction "22_22") (pintype "passive"))
      (node (ref "STM1") (pin "41") (pinfunction "PE10_41") (pintype "passive"))
    )
    (net (code "90") (name "/PE11") (class "Default")
      (node (ref "P3") (pin "19") (pinfunction "19_19") (pintype "passive"))
      (node (ref "STM1") (pin "42") (pinfunction "PE11_42") (pintype "passive"))
    )
    (net (code "91") (name "/PE14") (class "Default")
      (node (ref "STM1") (pin "45") (pinfunction "PE14_45") (pintype "passive"))
    )
    (net (code "92") (name "/PE15") (class "Default")
      (node (ref "STM1") (pin "46") (pinfunction "PE15_46") (pintype "passive"))
    )
    (net (code "93") (name "/RESET") (class "Default")
      (node (ref "C11") (pin "2") (pinfunction "2_2") (pintype "passive"))
      (node (ref "R1") (pin "2") (pinfunction "2_2") (pintype "passive"))
      (node (ref "RST1") (pin "1") (pinfunction "1_1") (pintype "passive"))
      (node (ref "STM1") (pin "14") (pinfunction "NRST_14") (pintype "passive"))
    )
    (net (code "94") (name "/Relay1") (class "Default")
      (node (ref "R24") (pin "2") (pinfunction "2_2") (pintype "passive"))
    )
    (net (code "95") (name "/Relay2") (class "Default")
      (node (ref "R25") (pin "2") (pinfunction "2_2") (pintype "passive"))
    )
    (net (code "96") (name "/USART_RX") (class "Default")
      (node (ref "P7") (pin "4") (pinfunction "4_4") (pintype "passive"))
      (node (ref "U2") (pin "3") (pinfunction "MCU_RX_3") (pintype "passive"))
    )
    (net (code "97") (name "/USART_TX") (class "Default")
      (node (ref "P7") (pin "3") (pinfunction "3_3") (pintype "passive"))
      (node (ref "U2") (pin "4") (pinfunction "MCU_TX_4") (pintype "passive"))
    )
    (net (code "98") (name "/VCC5_IN") (class "Default")
      (node (ref "P6") (pin "1") (pinfunction "1_1") (pintype "passive"))
      (node (ref "USB1") (pin "1") (pinfunction "V+_1") (pintype "passive"))
    )
    (net (code "99") (name "GND") (class "Default")
      (node (ref "C1") (pin "1") (pinfunction "1_1") (pintype "passive"))
      (node (ref "C10") (pin "1") (pinfunction "1_1") (pintype "passive"))
      (node (ref "C11") (pin "1") (pinfunction "1_1") (pintype "passive"))
      (node (ref "C12") (pin "1") (pinfunction "1_1") (pintype "passive"))
      (node (ref "C13") (pin "1") (pinfunction "1_1") (pintype "passive"))
      (node (ref "C14") (pin "1") (pinfunction "1_1") (pintype "passive"))
      (node (ref "C15") (pin "1") (pinfunction "1_1") (pintype "passive"))
      (node (ref "C16") (pin "1") (pinfunction "1_1") (pintype "passive"))
      (node (ref "C17") (pin "1") (pinfunction "1_1") (pintype "passive"))
      (node (ref "C2") (pin "1") (pinfunction "1_1") (pintype "passive"))
      (node (ref "C3") (pin "1") (pinfunction "1_1") (pintype "passive"))
      (node (ref "C4") (pin "1") (pinfunction "1_1") (pintype "passive"))
      (node (ref "C5") (pin "1") (pinfunction "1_1") (pintype "passive"))
      (node (ref "C9") (pin "1") (pinfunction "1_1") (pintype "passive"))
      (node (ref "D8") (pin "2") (pinfunction "K_2") (pintype "passive"))
      (node (ref "ESP_RST1") (pin "2") (pinfunction "2_2") (pintype "passive"))
      (node (ref "KEY1") (pin "1") (pinfunction "1_1") (pintype "passive"))
      (node (ref "KEY2") (pin "1") (pinfunction "1_1") (pintype "passive"))
      (node (ref "L2") (pin "1") (pinfunction "1_1") (pintype "passive"))
      (node (ref "P1") (pin "5") (pinfunction "5_5") (pintype "passive"))
      (node (ref "P1") (pin "6") (pinfunction "6_6") (pintype "passive"))
      (node (ref "P4") (pin "1") (pinfunction "1_1") (pintype "passive"))
      (node (ref "P5") (pin "1") (pinfunction "1_1") (pintype "passive"))
      (node (ref "Q1") (pin "3") (pinfunction "E_3") (pintype "passive"))
      (node (ref "Q2") (pin "3") (pinfunction "E_3") (pintype "passive"))
      (node (ref "Q3") (pin "3") (pinfunction "E_3") (pintype "passive"))
      (node (ref "R10") (pin "1") (pintype "passive"))
      (node (ref "R26") (pin "2") (pinfunction "2_2") (pintype "passive"))
      (node (ref "R27") (pin "2") (pinfunction "2_2") (pintype "passive"))
      (node (ref "R28") (pin "2") (pinfunction "2_2") (pintype "passive"))
      (node (ref "RST1") (pin "2") (pinfunction "2_2") (pintype "passive"))
      (node (ref "STM1") (pin "10") (pinfunction "VSS_10") (pintype "passive"))
      (node (ref "STM1") (pin "27") (pinfunction "VSS_27") (pintype "passive"))
      (node (ref "STM1") (pin "49") (pinfunction "VSS_49") (pintype "passive"))
      (node (ref "STM1") (pin "74") (pinfunction "VSS_74") (pintype "passive"))
      (node (ref "STM1") (pin "99") (pinfunction "VSS_99") (pintype "passive"))
      (node (ref "U1") (pin "1") (pinfunction "GND_1") (pintype "passive"))
      (node (ref "U2") (pin "8") (pinfunction "GND_8") (pintype "passive"))
      (node (ref "U3") (pin "4") (pinfunction "GND_4") (pintype "passive"))
      (node (ref "U4") (pin "1") (pinfunction "GND_1") (pintype "open_emitter"))
      (node (ref "USB1") (pin "5") (pinfunction "GND_5") (pintype "passive"))
    )
    (net (code "100") (name "Net-(BEEP1-B)") (class "Default")
      (node (ref "BEEP1") (pin "2") (pinfunction "B_2") (pintype "passive"))
      (node (ref "Q1") (pin "1") (pinfunction "C_1") (pintype "passive"))
    )
    (net (code "101") (name "Net-(D3-A)") (class "Default")
      (node (ref "D3") (pin "1") (pinfunction "A_1") (pintype "passive"))
      (node (ref "R15") (pin "2") (pinfunction "2_2") (pintype "passive"))
    )
    (net (code "102") (name "Net-(D4-A)") (class "Default")
      (node (ref "D4") (pin "1") (pinfunction "A_1") (pintype "passive"))
      (node (ref "R16") (pin "2") (pinfunction "2_2") (pintype "passive"))
    )
    (net (code "103") (name "Net-(D5-A)") (class "Default")
      (node (ref "D5") (pin "1") (pinfunction "A_1") (pintype "passive"))
      (node (ref "R18") (pin "2") (pinfunction "2_2") (pintype "passive"))
    )
    (net (code "104") (name "Net-(D6-A)") (class "Default")
      (node (ref "D6") (pin "1") (pinfunction "A_1") (pintype "passive"))
      (node (ref "R20") (pin "2") (pinfunction "2_2") (pintype "passive"))
    )
    (net (code "105") (name "Net-(D7-A)") (class "Default")
      (node (ref "D7") (pin "1") (pinfunction "A_1") (pintype "passive"))
      (node (ref "R21") (pin "2") (pinfunction "2_2") (pintype "passive"))
    )
    (net (code "106") (name "Net-(D8-A)") (class "Default")
      (node (ref "D8") (pin "1") (pinfunction "A_1") (pintype "passive"))
      (node (ref "R22") (pin "2") (pinfunction "2_2") (pintype "passive"))
    )
    (net (code "107") (name "Net-(P1-Pad3)") (class "Default")
      (node (ref "P1") (pin "3") (pinfunction "3_3") (pintype "passive"))
      (node (ref "R2") (pin "2") (pinfunction "2_2") (pintype "passive"))
    )
    (net (code "108") (name "Net-(P1-Pad4)") (class "Default")
      (node (ref "P1") (pin "4") (pinfunction "4_4") (pintype "passive"))
      (node (ref "R3") (pin "1") (pinfunction "1_1") (pintype "passive"))
    )
    (net (code "109") (name "Net-(Q1-B)") (class "Default")
      (node (ref "Q1") (pin "2") (pinfunction "B_2") (pintype "passive"))
      (node (ref "R23") (pin "1") (pinfunction "1_1") (pintype "passive"))
      (node (ref "R26") (pin "1") (pinfunction "1_1") (pintype "passive"))
    )
    (net (code "110") (name "Net-(Q2-B)") (class "Default")
      (node (ref "Q2") (pin "2") (pinfunction "B_2") (pintype "passive"))
      (node (ref "R24") (pin "1") (pinfunction "1_1") (pintype "passive"))
      (node (ref "R27") (pin "1") (pinfunction "1_1") (pintype "passive"))
    )
    (net (code "111") (name "Net-(Q2-C)") (class "Default")
      (node (ref "P8") (pin "2") (pinfunction "2_2") (pintype "passive"))
      (node (ref "Q2") (pin "1") (pinfunction "C_1") (pintype "passive"))
    )
    (net (code "112") (name "Net-(Q3-B)") (class "Default")
      (node (ref "Q3") (pin "2") (pinfunction "B_2") (pintype "passive"))
      (node (ref "R25") (pin "1") (pinfunction "1_1") (pintype "passive"))
      (node (ref "R28") (pin "1") (pinfunction "1_1") (pintype "passive"))
    )
    (net (code "113") (name "Net-(Q3-C)") (class "Default")
      (node (ref "P9") (pin "2") (pinfunction "2_2") (pintype "passive"))
      (node (ref "Q3") (pin "1") (pinfunction "C_1") (pintype "passive"))
    )
    (net (code "114") (name "Net-(U4-CH_PD)") (class "Default")
      (node (ref "R13") (pin "2") (pintype "passive"))
      (node (ref "U4") (pin "11") (pinfunction "CH_PD_11") (pintype "passive"))
    )
    (net (code "115") (name "Net-(U4-RXD)") (class "Default")
      (node (ref "D1") (pin "1") (pintype "passive"))
      (node (ref "R12") (pin "1") (pintype "passive"))
      (node (ref "U4") (pin "7") (pinfunction "RXD_7") (pintype "passive"))
    )
    (net (code "116") (name "Net-(U4-TXD)") (class "Default")
      (node (ref "D2") (pin "2") (pintype "passive"))
      (node (ref "U4") (pin "8") (pinfunction "TXD_8") (pintype "passive"))
    )
    (net (code "117") (name "Net-(USB1-D+)") (class "Default")
      (node (ref "R4") (pin "1") (pinfunction "1_1") (pintype "passive"))
      (node (ref "R6") (pin "1") (pinfunction "1_1") (pintype "passive"))
      (node (ref "USB1") (pin "3") (pinfunction "D+_3") (pintype "passive"))
    )
    (net (code "118") (name "Net-(USB1-D-)") (class "Default")
      (node (ref "R5") (pin "1") (pinfunction "1_1") (pintype "passive"))
      (node (ref "USB1") (pin "2") (pinfunction "D-_2") (pintype "passive"))
    )
    (net (code "119") (name "VCC3.3") (class "Default")
      (node (ref "BEEP1") (pin "1") (pinfunction "A_1") (pintype "passive"))
      (node (ref "C1") (pin "2") (pinfunction "2_2") (pintype "passive"))
      (node (ref "C10") (pin "2") (pinfunction "2_2") (pintype "passive"))
      (node (ref "C2") (pin "2") (pinfunction "2_2") (pintype "passive"))
      (node (ref "C3") (pin "2") (pinfunction "2_2") (pintype "passive"))
      (node (ref "C4") (pin "2") (pinfunction "2_2") (pintype "passive"))
      (node (ref "C5") (pin "2") (pinfunction "2_2") (pintype "passive"))
      (node (ref "L1") (pin "2") (pinfunction "2_2") (pintype "passive"))
      (node (ref "P1") (pin "1") (pinfunction "1_1") (pintype "passive"))
      (node (ref "P1") (pin "2") (pinfunction "2_2") (pintype "passive"))
      (node (ref "P4") (pin "2") (pinfunction "2_2") (pintype "passive"))
      (node (ref "P5") (pin "2") (pinfunction "2_2") (pintype "passive"))
      (node (ref "P8") (pin "1") (pinfunction "1_1") (pintype "passive"))
      (node (ref "P9") (pin "1") (pinfunction "1_1") (pintype "passive"))
      (node (ref "R1") (pin "1") (pinfunction "1_1") (pintype "passive"))
      (node (ref "R11") (pin "2") (pintype "passive"))
      (node (ref "R12") (pin "2") (pintype "passive"))
      (node (ref "R13") (pin "1") (pintype "passive"))
      (node (ref "R14") (pin "1") (pintype "passive"))
      (node (ref "R15") (pin "1") (pinfunction "1_1") (pintype "passive"))
      (node (ref "R16") (pin "1") (pinfunction "1_1") (pintype "passive"))
      (node (ref "R17") (pin "1") (pinfunction "1_1") (pintype "passive"))
      (node (ref "R18") (pin "1") (pinfunction "1_1") (pintype "passive"))
      (node (ref "R19") (pin "1") (pinfunction "1_1") (pintype "passive"))
      (node (ref "R20") (pin "1") (pinfunction "1_1") (pintype "passive"))
      (node (ref "R21") (pin "1") (pinfunction "1_1") (pintype "passive"))
      (node (ref "R22") (pin "1") (pinfunction "1_1") (pintype "passive"))
      (node (ref "R4") (pin "2") (pinfunction "2_2") (pintype "passive"))
      (node (ref "R8") (pin "2") (pintype "passive"))
      (node (ref "R9") (pin "1") (pintype "passive"))
      (node (ref "STM1") (pin "100") (pinfunction "VDD_100") (pintype "passive"))
      (node (ref "STM1") (pin "11") (pinfunction "VDD_11") (pintype "passive"))
      (node (ref "STM1") (pin "28") (pinfunction "VDD_28") (pintype "passive"))
      (node (ref "STM1") (pin "50") (pinfunction "VDD_50") (pintype "passive"))
      (node (ref "STM1") (pin "75") (pinfunction "VDD_75") (pintype "passive"))
      (node (ref "U1") (pin "2") (pinfunction "OUT_2") (pintype "passive"))
      (node (ref "U4") (pin "16") (pinfunction "VCC_16") (pintype "passive"))
    )
    (net (code "120") (name "VCC5") (class "Default")
      (node (ref "C9") (pin "2") (pinfunction "2_2") (pintype "passive"))
      (node (ref "P6") (pin "2") (pinfunction "2_2") (pintype "passive"))
      (node (ref "U1") (pin "3") (pinfunction "VCC_3") (pintype "passive"))
      (node (ref "U2") (pin "19") (pinfunction "VCC_19") (pintype "passive"))
      (node (ref "U2") (pin "5") (pinfunction "VCC_5") (pintype "passive"))
      (node (ref "U3") (pin "1") (pinfunction "VDD_1") (pintype "passive"))
    )
    (net (code "121") (name "VDDA") (class "Default")
      (node (ref "C6") (pin "1") (pinfunction "1_1") (pintype "passive"))
      (node (ref "C7") (pin "1") (pinfunction "1_1") (pintype "passive"))
      (node (ref "C8") (pin "2") (pinfunction "2_2") (pintype "passive"))
      (node (ref "L1") (pin "1") (pinfunction "1_1") (pintype "passive"))
      (node (ref "STM1") (pin "22") (pinfunction "VDDA_22") (pintype "passive"))
    )
    (net (code "122") (name "VSSA") (class "Default")
      (node (ref "C6") (pin "2") (pinfunction "2_2") (pintype "passive"))
      (node (ref "C7") (pin "2") (pinfunction "2_2") (pintype "passive"))
      (node (ref "C8") (pin "1") (pinfunction "1_1") (pintype "passive"))
      (node (ref "L2") (pin "2") (pinfunction "2_2") (pintype "passive"))
      (node (ref "STM1") (pin "19") (pinfunction "VSSA_19") (pintype "passive"))
    )
    (net (code "123") (name "unconnected-(P2-Pad29)") (class "Default")
      (node (ref "P2") (pin "29") (pinfunction "29_29") (pintype "passive"))
    )
    (net (code "124") (name "unconnected-(P2-Pad31)") (class "Default")
      (node (ref "P2") (pin "31") (pinfunction "31_31") (pintype "passive"))
    )
    (net (code "125") (name "unconnected-(P2-Pad32)") (class "Default")
      (node (ref "P2") (pin "32") (pinfunction "32_32") (pintype "passive"))
    )
    (net (code "126") (name "unconnected-(P6-Pad3)") (class "Default")
      (node (ref "P6") (pin "3") (pinfunction "3_3") (pintype "passive"))
    )
    (net (code "127") (name "unconnected-(P6-Pad4)") (class "Default")
      (node (ref "P6") (pin "4") (pinfunction "4_4") (pintype "passive"))
    )
    (net (code "128") (name "unconnected-(P6-Pad5)") (class "Default")
      (node (ref "P6") (pin "5") (pinfunction "5_5") (pintype "passive"))
    )
    (net (code "129") (name "unconnected-(P6-Pad6)") (class "Default")
      (node (ref "P6") (pin "6") (pinfunction "6_6") (pintype "passive"))
    )
    (net (code "130") (name "unconnected-(STM1-NC-Pad73)") (class "Default")
      (node (ref "STM1") (pin "73") (pinfunction "NC_73") (pintype "passive"))
    )
    (net (code "131") (name "unconnected-(STM1-VBAT-Pad6)") (class "Default")
      (node (ref "STM1") (pin "6") (pinfunction "VBAT_6") (pintype "passive"))
    )
    (net (code "132") (name "unconnected-(STM1-VREF+-Pad21)") (class "Default")
      (node (ref "STM1") (pin "21") (pinfunction "VREF+_21") (pintype "passive"))
    )
    (net (code "133") (name "unconnected-(STM1-VREF--Pad20)") (class "Default")
      (node (ref "STM1") (pin "20") (pinfunction "VREF-_20") (pintype "passive"))
    )
    (net (code "134") (name "unconnected-(U2-NC{slash}CLK_OUT-Pad1)") (class "Default")
      (node (ref "U2") (pin "1") (pinfunction "NC/CLK_OUT_1") (pintype "passive"))
    )
    (net (code "135") (name "unconnected-(U3-NC-Pad3)") (class "Default")
      (node (ref "U3") (pin "3") (pinfunction "NC_3") (pintype "passive"))
    )
    (net (code "136") (name "unconnected-(U4-ADC-Pad10)") (class "Default")
      (node (ref "U4") (pin "10") (pinfunction "ADC_10") (pintype "passive"))
    )
    (net (code "137") (name "unconnected-(U4-GPIO2-Pad3)") (class "Default")
      (node (ref "U4") (pin "3") (pinfunction "GPIO2_3") (pintype "passive"))
    )
    (net (code "138") (name "unconnected-(U4-GPIO4-Pad6)") (class "Default")
      (node (ref "U4") (pin "6") (pinfunction "GPIO4_6") (pintype "passive"))
    )
    (net (code "139") (name "unconnected-(U4-GPIO5-Pad5)") (class "Default")
      (node (ref "U4") (pin "5") (pinfunction "GPIO5_5") (pintype "passive"))
    )
    (net (code "140") (name "unconnected-(U4-GPIO9-Pad22)") (class "Default")
      (node (ref "U4") (pin "22") (pinfunction "GPIO9_22") (pintype "passive"))
    )
    (net (code "141") (name "unconnected-(U4-GPIO10-Pad19)") (class "Default")
      (node (ref "U4") (pin "19") (pinfunction "GPIO10_19") (pintype "passive"))
    )
    (net (code "142") (name "unconnected-(U4-GPIO12-Pad14)") (class "Default")
      (node (ref "U4") (pin "14") (pinfunction "GPIO12_14") (pintype "passive"))
    )
    (net (code "143") (name "unconnected-(U4-GPIO13-Pad15)") (class "Default")
      (node (ref "U4") (pin "15") (pinfunction "GPIO13_15") (pintype "passive"))
    )
    (net (code "144") (name "unconnected-(U4-GPIO14-Pad13)") (class "Default")
      (node (ref "U4") (pin "13") (pinfunction "GPIO14_13") (pintype "passive"))
    )
    (net (code "145") (name "unconnected-(U4-GPIO16-Pad12)") (class "Default")
      (node (ref "U4") (pin "12") (pinfunction "GPIO16_12") (pintype "passive"))
    )
    (net (code "146") (name "unconnected-(U4-MTCK-Pad21)") (class "Default")
      (node (ref "U4") (pin "21") (pinfunction "MTCK_21") (pintype "passive"))
    )
    (net (code "147") (name "unconnected-(U4-MTDI-Pad18)") (class "Default")
      (node (ref "U4") (pin "18") (pinfunction "MTDI_18") (pintype "passive"))
    )
    (net (code "148") (name "unconnected-(U4-MTDO-Pad17)") (class "Default")
      (node (ref "U4") (pin "17") (pinfunction "MTDO_17") (pintype "passive"))
    )
    (net (code "149") (name "unconnected-(U4-MTMS-Pad20)") (class "Default")
      (node (ref "U4") (pin "20") (pinfunction "MTMS_20") (pintype "passive"))
    )
    (net (code "150") (name "unconnected-(USB1-ID-Pad4)") (class "Default")
      (node (ref "USB1") (pin "4") (pinfunction "ID_4") (pintype "passive"))
    )
  )
)
